# Beagle_3V_SPI_Oled_Rev1.net
KiCad netlist of a schematic drawn in Altium Designer
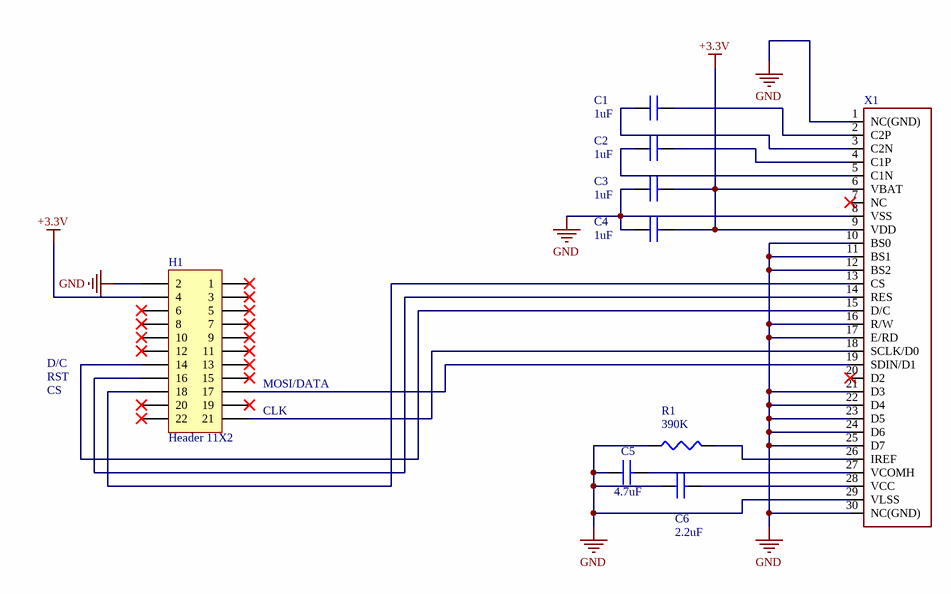
[diagram p0: Beagle_3V_SPI_Oled_Rev1.SchDoc]

(export (version "E")
  (design (tool "Eeschema 10.0.6"))
  (components
    (comp (ref "C1")
      (value "1uF")
      (footprint "CAPC1608X90N")
      (description "1uf, 0603, X7R, 25V")
      (fields (field (name "PARTNUMBER") "GRM188R71E105KA12D") (field (name "MANUFACTURER") "Murata"))
      (libsource (lib "Parts_Library") (part "CAP_0603"))
    )
    (comp (ref "C2")
      (value "1uF")
      (footprint "CAPC1608X90N")
      (description "1uf, 0603, X7R, 25V")
      (fields (field (name "PARTNUMBER") "GRM188R71E105KA12D") (field (name "MANUFACTURER") "Murata"))
      (libsource (lib "Parts_Library") (part "CAP_0603"))
    )
    (comp (ref "C3")
      (value "1uF")
      (footprint "CAPC1608X90N")
      (description "1uf, 0603, X7R, 25V")
      (fields (field (name "PARTNUMBER") "GRM188R71E105KA12D") (field (name "MANUFACTURER") "Murata"))
      (libsource (lib "Parts_Library") (part "CAP_0603"))
    )
    (comp (ref "C4")
      (value "1uF")
      (footprint "CAPC1608X90N")
      (description "1uf, 0603, X7R, 25V")
      (fields (field (name "PARTNUMBER") "GRM188R71E105KA12D") (field (name "MANUFACTURER") "Murata"))
      (libsource (lib "Parts_Library") (part "CAP_0603"))
    )
    (comp (ref "C5")
      (value "4.7uF")
      (footprint "CAPC1608X90N")
      (description "4.7uf, 0603, X5R, 25V")
      (fields (field (name "PARTNUMBER") "GRM188R61E475KE11D") (field (name "MANUFACTURER") "Murata"))
      (libsource (lib "Parts_Library") (part "CAP_0603"))
    )
    (comp (ref "C6")
      (value "2.2uF")
      (footprint "CAPC1608X90N")
      (description "2.2uf, 0603, X5R, 25V")
      (fields (field (name "PARTNUMBER") "GRM188R61E225KA12D") (field (name "MANUFACTURER") "Murata"))
      (libsource (lib "Parts_Library") (part "CAP_0603"))
    )
    (comp (ref "H1")
      (value "Header 11X2")
      (footprint "HDR2X11")
      (description "22 Position Header Connector 0.100\"")
      (fields (field (name "MANUFACTURER") "Sullins") (field (name "PARTNUMBER") "PPTC112LFBN-RC"))
      (libsource (lib "Miscellaneous Connectors") (part "Header 11X2"))
    )
    (comp (ref "R1")
      (value "390K")
      (footprint "RESC1608X55N")
      (description "RES SMD 390K OHM 1% 1/10W 0603")
      (fields (field (name "MANUFACTURER") "Panasonic") (field (name "PARTNUMBER") "ERJ-3EKF3903V"))
      (libsource (lib "Parts_Library") (part "RES_0603"))
    )
    (comp (ref "X1")
      (value "OLED_GLASS")
      (footprint "OLED_GLASS")
      (fields (field (name "PARTNUMBER") "ER-OLED0.96-1W") (field (name "MANUFACTURER") "Buy-Display"))
      (libsource (lib "Parts_Library") (part "OLED_GLASS"))
    )
  )
  (nets
    (net (code "1") (name "+3.3V") (class "Default")
      (node (ref "C3") (pin "2") (pinfunction "2_2") (pintype "passive"))
      (node (ref "C4") (pin "2") (pinfunction "2_2") (pintype "passive"))
      (node (ref "H1") (pin "4") (pinfunction "4_4") (pintype "passive"))
      (node (ref "X1") (pin "6") (pinfunction "VBAT_6") (pintype "passive"))
      (node (ref "X1") (pin "9") (pinfunction "VDD_9") (pintype "passive"))
    )
    (net (code "2") (name "GND") (class "Default")
      (node (ref "C3") (pin "1") (pinfunction "1_1") (pintype "passive"))
      (node (ref "C4") (pin "1") (pinfunction "1_1") (pintype "passive"))
      (node (ref "C5") (pin "1") (pinfunction "1_1") (pintype "passive"))
      (node (ref "C6") (pin "1") (pinfunction "1_1") (pintype "passive"))
      (node (ref "H1") (pin "2") (pinfunction "2_2") (pintype "passive"))
      (node (ref "R1") (pin "1") (pinfunction "1_1") (pintype "passive"))
      (node (ref "X1") (pin "1") (pinfunction "NC(GND)_1") (pintype "passive"))
      (node (ref "X1") (pin "10") (pinfunction "BS0_10") (pintype "passive"))
      (node (ref "X1") (pin "11") (pinfunction "BS1_11") (pintype "passive"))
      (node (ref "X1") (pin "12") (pinfunction "BS2_12") (pintype "passive"))
      (node (ref "X1") (pin "16") (pinfunction "R/W_16") (pintype "passive"))
      (node (ref "X1") (pin "17") (pinfunction "E/RD_17") (pintype "passive"))
      (node (ref "X1") (pin "21") (pinfunction "D3_21") (pintype "passive"))
      (node (ref "X1") (pin "22") (pinfunction "D4_22") (pintype "passive"))
      (node (ref "X1") (pin "23") (pinfunction "D5_23") (pintype "passive"))
      (node (ref "X1") (pin "24") (pinfunction "D6_24") (pintype "passive"))
      (node (ref "X1") (pin "25") (pinfunction "D7_25") (pintype "passive"))
      (node (ref "X1") (pin "29") (pinfunction "VLSS_29") (pintype "passive"))
      (node (ref "X1") (pin "30") (pinfunction "NC(GND)_30") (pintype "passive"))
      (node (ref "X1") (pin "8") (pinfunction "VSS_8") (pintype "passive"))
    )
    (net (code "3") (name "Net-(X1-C1N)") (class "Default")
      (node (ref "C2") (pin "1") (pinfunction "1_1") (pintype "passive"))
      (node (ref "X1") (pin "5") (pinfunction "C1N_5") (pintype "passive"))
    )
    (net (code "4") (name "Net-(X1-C1P)") (class "Default")
      (node (ref "C2") (pin "2") (pinfunction "2_2") (pintype "passive"))
      (node (ref "X1") (pin "4") (pinfunction "C1P_4") (pintype "passive"))
    )
    (net (code "5") (name "Net-(X1-C2N)") (class "Default")
      (node (ref "C1") (pin "1") (pinfunction "1_1") (pintype "passive"))
      (node (ref "X1") (pin "3") (pinfunction "C2N_3") (pintype "passive"))
    )
    (net (code "6") (name "Net-(X1-C2P)") (class "Default")
      (node (ref "C1") (pin "2") (pinfunction "2_2") (pintype "passive"))
      (node (ref "X1") (pin "2") (pinfunction "C2P_2") (pintype "passive"))
    )
    (net (code "7") (name "Net-(X1-CS)") (class "Default")
      (node (ref "H1") (pin "18") (pinfunction "18_18") (pintype "passive"))
      (node (ref "X1") (pin "13") (pinfunction "CS_13") (pintype "passive"))
    )
    (net (code "8") (name "Net-(X1-D{slash}C)") (class "Default")
      (node (ref "H1") (pin "14") (pinfunction "14_14") (pintype "passive"))
      (node (ref "X1") (pin "15") (pinfunction "D/C_15") (pintype "passive"))
    )
    (net (code "9") (name "Net-(X1-IREF)") (class "Default")
      (node (ref "R1") (pin "2") (pinfunction "2_2") (pintype "passive"))
      (node (ref "X1") (pin "26") (pinfunction "IREF_26") (pintype "passive"))
    )
    (net (code "10") (name "Net-(X1-RES)") (class "Default")
      (node (ref "H1") (pin "16") (pinfunction "16_16") (pintype "passive"))
      (node (ref "X1") (pin "14") (pinfunction "RES_14") (pintype "passive"))
    )
    (net (code "11") (name "Net-(X1-SCLK{slash}D0)") (class "Default")
      (node (ref "H1") (pin "21") (pinfunction "21_21") (pintype "passive"))
      (node (ref "X1") (pin "18") (pinfunction "SCLK/D0_18") (pintype "passive"))
    )
    (net (code "12") (name "Net-(X1-SDIN{slash}D1)") (class "Default")
      (node (ref "H1") (pin "17") (pinfunction "17_17") (pintype "passive"))
      (node (ref "X1") (pin "19") (pinfunction "SDIN/D1_19") (pintype "passive"))
    )
    (net (code "13") (name "Net-(X1-VCC)") (class "Default")
      (node (ref "C6") (pin "2") (pinfunction "2_2") (pintype "passive"))
      (node (ref "X1") (pin "28") (pinfunction "VCC_28") (pintype "passive"))
    )
    (net (code "14") (name "Net-(X1-VCOMH)") (class "Default")
      (node (ref "C5") (pin "2") (pinfunction "2_2") (pintype "passive"))
      (node (ref "X1") (pin "27") (pinfunction "VCOMH_27") (pintype "passive"))
    )
    (net (code "15") (name "unconnected-(H1-Pad1)") (class "Default")
      (node (ref "H1") (pin "1") (pinfunction "1_1") (pintype "passive+no_connect"))
    )
    (net (code "16") (name "unconnected-(H1-Pad3)") (class "Default")
      (node (ref "H1") (pin "3") (pinfunction "3_3") (pintype "passive+no_connect"))
    )
    (net (code "17") (name "unconnected-(H1-Pad5)") (class "Default")
      (node (ref "H1") (pin "5") (pinfunction "5_5") (pintype "passive+no_connect"))
    )
    (net (code "18") (name "unconnected-(H1-Pad6)") (class "Default")
      (node (ref "H1") (pin "6") (pinfunction "6_6") (pintype "passive+no_connect"))
    )
    (net (code "19") (name "unconnected-(H1-Pad7)") (class "Default")
      (node (ref "H1") (pin "7") (pinfunction "7_7") (pintype "passive+no_connect"))
    )
    (net (code "20") (name "unconnected-(H1-Pad8)") (class "Default")
      (node (ref "H1") (pin "8") (pinfunction "8_8") (pintype "passive+no_connect"))
    )
    (net (code "21") (name "unconnected-(H1-Pad9)") (class "Default")
      (node (ref "H1") (pin "9") (pinfunction "9_9") (pintype "passive+no_connect"))
    )
    (net (code "22") (name "unconnected-(H1-Pad10)") (class "Default")
      (node (ref "H1") (pin "10") (pinfunction "10_10") (pintype "passive+no_connect"))
    )
    (net (code "23") (name "unconnected-(H1-Pad11)") (class "Default")
      (node (ref "H1") (pin "11") (pinfunction "11_11") (pintype "passive+no_connect"))
    )
    (net (code "24") (name "unconnected-(H1-Pad12)") (class "Default")
      (node (ref "H1") (pin "12") (pinfunction "12_12") (pintype "passive+no_connect"))
    )
    (net (code "25") (name "unconnected-(H1-Pad13)") (class "Default")
      (node (ref "H1") (pin "13") (pinfunction "13_13") (pintype "passive+no_connect"))
    )
    (net (code "26") (name "unconnected-(H1-Pad15)") (class "Default")
      (node (ref "H1") (pin "15") (pinfunction "15_15") (pintype "passive+no_connect"))
    )
    (net (code "27") (name "unconnected-(H1-Pad19)") (class "Default")
      (node (ref "H1") (pin "19") (pinfunction "19_19") (pintype "passive+no_connect"))
    )
    (net (code "28") (name "unconnected-(H1-Pad20)") (class "Default")
      (node (ref "H1") (pin "20") (pinfunction "20_20") (pintype "passive+no_connect"))
    )
    (net (code "29") (name "unconnected-(H1-Pad22)") (class "Default")
      (node (ref "H1") (pin "22") (pinfunction "22_22") (pintype "passive+no_connect"))
    )
    (net (code "30") (name "unconnected-(X1-D2-Pad20)") (class "Default")
      (node (ref "X1") (pin "20") (pinfunction "D2_20") (pintype "passive+no_connect"))
    )
    (net (code "31") (name "unconnected-(X1-NC-Pad7)") (class "Default")
      (node (ref "X1") (pin "7") (pinfunction "NC_7") (pintype "passive+no_connect"))
    )
  )
)
